# overall.net
KiCad netlist of a schematic drawn in Altium Designer
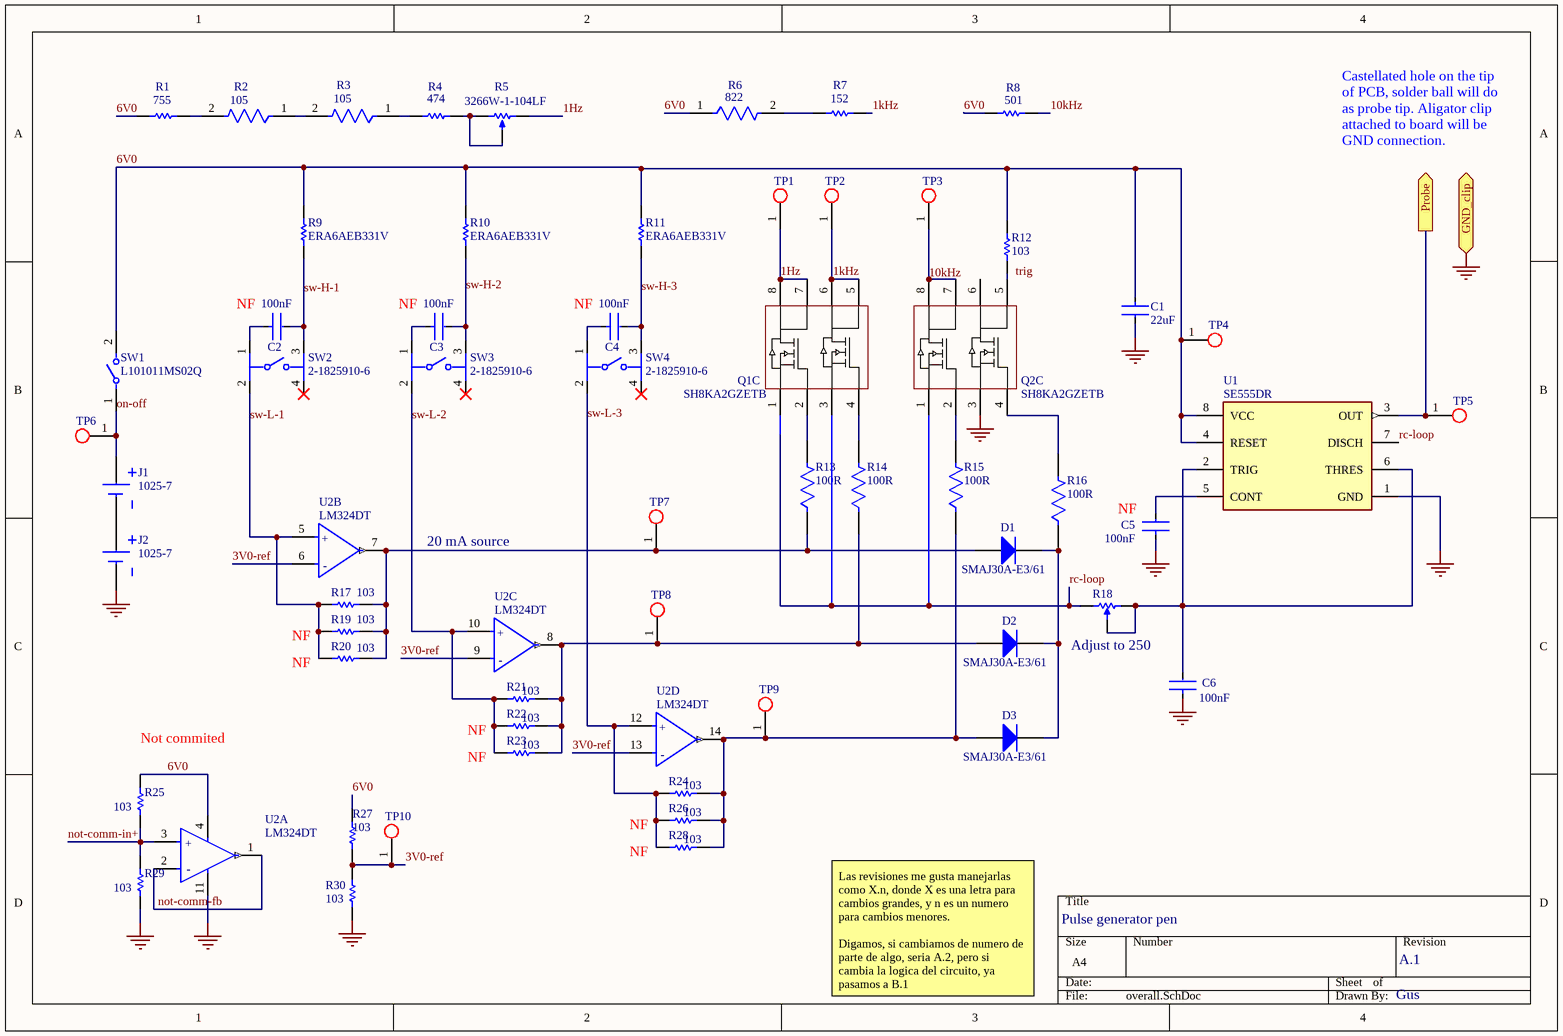
[diagram p0: overall.SchDoc]

(export (version "E")
  (design (tool "Eeschema 10.0.6"))
  (components
    (comp (ref "C1")
      (value "C2012X5R1V226M125AC")
      (footprint "FP-C2012-125-0_2-IPC_A")
      (description "Multilayer Ceramic Capacitors 22μF ±20% 35V X5R SMD 0805")
      (fields (field (name "TOLERANCE") "20%") (field (name "CAPACITANCE") "22uF"))
      (libsource (lib "Altium Content Vault") (part "b4654b650e69147ec39a6b967a45e02"))
    )
    (comp (ref "C2")
      (value "CL21B104KBCNNNC")
      (footprint "FP-CL21-IPC_A")
      (description "CL21 Series 0805 100nF 50V ±10% Tolerance X7R Multilayer Ceramic Chip Capacitor")
      (fields
        (field (name "TOLERANCE") "10%")
        (field (name "CAPACITANCE") "100nF")
        (field (name "VOLTAGE") "50V")
      )
      (libsource (lib "Altium Content Vault") (part "b4654b650e69147ec39a6b967a45e02"))
    )
    (comp (ref "C3")
      (value "CL21B104KBCNNNC")
      (footprint "FP-CL21-IPC_A")
      (description "CL21 Series 0805 100nF 50V ±10% Tolerance X7R Multilayer Ceramic Chip Capacitor")
      (fields
        (field (name "TOLERANCE") "10%")
        (field (name "CAPACITANCE") "100nF")
        (field (name "VOLTAGE") "50V")
      )
      (libsource (lib "Altium Content Vault") (part "b4654b650e69147ec39a6b967a45e02"))
    )
    (comp (ref "C4")
      (value "CL21B104KBCNNNC")
      (footprint "FP-CL21-IPC_A")
      (description "CL21 Series 0805 100nF 50V ±10% Tolerance X7R Multilayer Ceramic Chip Capacitor")
      (fields
        (field (name "TOLERANCE") "10%")
        (field (name "CAPACITANCE") "100nF")
        (field (name "VOLTAGE") "50V")
      )
      (libsource (lib "Altium Content Vault") (part "b4654b650e69147ec39a6b967a45e02"))
    )
    (comp (ref "C5")
      (value "CL21B104KBCNNNC")
      (footprint "FP-CL21-IPC_A")
      (description "CL21 Series 0805 100nF 50V ±10% Tolerance X7R Multilayer Ceramic Chip Capacitor")
      (fields
        (field (name "TOLERANCE") "10%")
        (field (name "CAPACITANCE") "100nF")
        (field (name "VOLTAGE") "50V")
      )
      (libsource (lib "Altium Content Vault") (part "b4654b650e69147ec39a6b967a45e02"))
    )
    (comp (ref "C6")
      (value "CL21B104KBCNNNC")
      (footprint "FP-CL21-IPC_A")
      (description "CL21 Series 0805 100nF 50V ±10% Tolerance X7R Multilayer Ceramic Chip Capacitor")
      (fields
        (field (name "TOLERANCE") "10%")
        (field (name "CAPACITANCE") "100nF")
        (field (name "VOLTAGE") "50V")
      )
      (libsource (lib "Altium Content Vault") (part "b4654b650e69147ec39a6b967a45e02"))
    )
    (comp (ref "D1")
      (value "SMAJ30A-E3/61")
      (footprint "VISH-DO-214AC-2_N")
      (fields (field (name "MANUFACTURER") "Vishay Semiconductor"))
      (libsource (lib "Altium Content Vault") (part "VISH-K1A2-2"))
    )
    (comp (ref "D2")
      (value "SMAJ30A-E3/61")
      (footprint "VISH-DO-214AC-2_N")
      (fields (field (name "MANUFACTURER") "Vishay Semiconductor"))
      (libsource (lib "Altium Content Vault") (part "VISH-K1A2-2"))
    )
    (comp (ref "D3")
      (value "SMAJ30A-E3/61")
      (footprint "VISH-DO-214AC-2_N")
      (fields (field (name "MANUFACTURER") "Vishay Semiconductor"))
      (libsource (lib "Altium Content Vault") (part "VISH-K1A2-2"))
    )
    (comp (ref "J1")
      (value "1025-7")
      (footprint "KEYSTONE-1025-7-2_V")
      (description "Holder for 2477 or 2430 Cells P/N 1025-7, Body 27.762 x 30.963 mm, THM")
      (fields (field (name "MANUFACTURER") "Keystone"))
      (libsource (lib "Altium Content Vault") (part "KEYSTONE-1025-7-2"))
    )
    (comp (ref "J2")
      (value "1025-7")
      (footprint "KEYSTONE-1025-7-2_V")
      (description "Holder for 2477 or 2430 Cells P/N 1025-7, Body 27.762 x 30.963 mm, THM")
      (fields (field (name "MANUFACTURER") "Keystone"))
      (libsource (lib "Altium Content Vault") (part "KEYSTONE-1025-7-2"))
    )
    (comp (ref "Q1")
      (value "SH8KA2GZETB")
      (footprint "SOIC127P600X175-8N")
      (libsource (lib "Cetys University") (part "SH8KA2GZETB"))
    )
    (comp (ref "Q2")
      (value "SH8KA2GZETB")
      (footprint "SOIC127P600X175-8N")
      (libsource (lib "Cetys University") (part "SH8KA2GZETB"))
    )
    (comp (ref "R1")
      (value "CRCW08057M50JNEA")
      (footprint "RESC2013X50X30LL20T20")
      (fields (field (name "MANUFACTURER") "Vishay Dale") (field (name "RESISTANCE") "755"))
      (libsource (lib "Altium Content Vault") (part "RES"))
    )
    (comp (ref "R2")
      (value "ERJ-6ENF1004V")
      (footprint "FP-ERJ6EN-IPC_A")
      (description "RES SMD 1M OHM 1% 1/8W 0805")
      (fields (field (name "RESISTANCE") "105") (field (name "TOLERANCE") "1%"))
      (libsource (lib "Altium Content Vault") (part "1029c3af85768c4190bb7ad29bc67b5"))
    )
    (comp (ref "R3")
      (value "ERJ-6ENF1004V")
      (footprint "FP-ERJ6EN-IPC_A")
      (description "RES SMD 1M OHM 1% 1/8W 0805")
      (fields (field (name "RESISTANCE") "105") (field (name "TOLERANCE") "1%"))
      (libsource (lib "Altium Content Vault") (part "1029c3af85768c4190bb7ad29bc67b5"))
    )
    (comp (ref "R4")
      (value "ERJ6ENF4703V")
      (footprint "RESC2013X70X40ML20T20")
      (fields (field (name "MANUFACTURER") "Panasonic") (field (name "RESISTANCE") "474"))
      (libsource (lib "Altium Content Vault") (part "RES"))
    )
    (comp (ref "R5")
      (value "3266W-1-104LF")
      (footprint "BOUR-3266W-3_V")
      (description "Square Trimpot Trimming Potentiometer, 100 KOhm, 0.25 W, -55 to 125 degC, 3-Pin THD, RoHS, Tube")
      (fields (field (name "TOLERANCE") "+/-10%") (field (name "MANUFACTURER") "Bourns"))
      (libsource (lib "Altium Content Vault") (part "BOUR-POT-3"))
    )
    (comp (ref "R6")
      (value "RC2012J822CS")
      (footprint "FP-RC2012-IPC_A")
      (description "Res Thick Film 0805 8.2kΩ 5% 0.125W ±100ppm/°C Molded SMD T/R")
      (fields (field (name "RESISTANCE") "822") (field (name "TOLERANCE") "5%"))
      (libsource (lib "Altium Content Vault") (part "1029c3af85768c4190bb7ad29bc67b5"))
    )
    (comp (ref "R7")
      (value "RC0805FR-071K5L")
      (footprint "RESC2013X60X35LL10T20")
      (description "RES 1.50K OHM 1/8W 1% 0805 SMD")
      (fields (field (name "MANUFACTURER") "Yageo") (field (name "RESISTANCE") "152"))
      (libsource (lib "") (part "RES-2_1"))
    )
    (comp (ref "R8")
      (value "WSLP0805R0500FEA")
      (footprint "RESC2013X58X38LL25T25")
      (fields (field (name "MANUFACTURER") "Vishay Dale") (field (name "RESISTANCE") "501"))
      (libsource (lib "Altium Content Vault") (part "RES"))
    )
    (comp (ref "R9")
      (value "ERA6AEB331V")
      (footprint "RESC2013X60X40LL20T25")
      (fields (field (name "MANUFACTURER") "Panasonic"))
      (libsource (lib "Altium Content Vault") (part "RES"))
    )
    (comp (ref "R10")
      (value "ERA6AEB331V")
      (footprint "RESC2013X60X40LL20T25")
      (fields (field (name "MANUFACTURER") "Panasonic"))
      (libsource (lib "Altium Content Vault") (part "RES"))
    )
    (comp (ref "R11")
      (value "ERA6AEB331V")
      (footprint "RESC2013X60X40LL20T25")
      (fields (field (name "MANUFACTURER") "Panasonic"))
      (libsource (lib "Altium Content Vault") (part "RES"))
    )
    (comp (ref "R12")
      (value "RC0805FR-0710KL")
      (footprint "RESC2013X60X35NL10T20")
      (description "Chip Resistor, 10 KOhm, +/- 1%, 0.125 W, -55 to 155 degC, 0805 (2012 Metric), RoHS, Tape and Reel")
      (fields (field (name "MANUFACTURER") "Yageo") (field (name "RESISTANCE") "103"))
      (libsource (lib "Altium Content Vault") (part "RES-2"))
    )
    (comp (ref "R13")
      (value "CRCW0805100RFKEAHP")
      (footprint "FP-CRCW0805-HPe3-IPC_A")
      (description "RES Thick Film, 100Ω, 1%, 0.5W, 100ppm/°C, 0805")
      (fields (field (name "TOLERANCE") "1%") (field (name "RESISTANCE") "100R"))
      (libsource (lib "") (part "1029c3af85768c4190bb7ad29bc67b5_1"))
    )
    (comp (ref "R14")
      (value "CRCW0805100RFKEAHP")
      (footprint "FP-CRCW0805-HPe3-IPC_A")
      (description "RES Thick Film, 100Ω, 1%, 0.5W, 100ppm/°C, 0805")
      (fields (field (name "TOLERANCE") "1%") (field (name "RESISTANCE") "100R"))
      (libsource (lib "") (part "1029c3af85768c4190bb7ad29bc67b5_1"))
    )
    (comp (ref "R15")
      (value "CRCW0805100RFKEAHP")
      (footprint "FP-CRCW0805-HPe3-IPC_A")
      (description "RES Thick Film, 100Ω, 1%, 0.5W, 100ppm/°C, 0805")
      (fields (field (name "TOLERANCE") "1%") (field (name "RESISTANCE") "100R"))
      (libsource (lib "") (part "1029c3af85768c4190bb7ad29bc67b5_1"))
    )
    (comp (ref "R16")
      (value "CRCW0805100RFKEAHP")
      (footprint "FP-CRCW0805-HPe3-IPC_A")
      (description "RES Thick Film, 100Ω, 1%, 0.5W, 100ppm/°C, 0805")
      (fields (field (name "TOLERANCE") "1%") (field (name "RESISTANCE") "100R"))
      (libsource (lib "") (part "1029c3af85768c4190bb7ad29bc67b5_1"))
    )
    (comp (ref "R17")
      (value "RC0805FR-0710KL")
      (footprint "RESC2013X60X35NL10T20")
      (description "Chip Resistor, 10 KOhm, +/- 1%, 0.125 W, -55 to 155 degC, 0805 (2012 Metric), RoHS, Tape and Reel")
      (fields (field (name "MANUFACTURER") "Yageo") (field (name "RESISTANCE") "103"))
      (libsource (lib "Altium Content Vault") (part "RES-2"))
    )
    (comp (ref "R18")
      (value "3296W-1-102LF")
      (footprint "BOUR-3296W-1-3")
      (description "Square Trimpot(R) Trimming Potentiometer, 1000 Ohm, -55 to 125 degC, 3-Pin THD, RoHS, Tube")
      (fields (field (name "TOLERANCE") "1%"))
      (libsource (lib "Altium Content Vault") (part "RES-ADJ-3"))
    )
    (comp (ref "R19")
      (value "RC0805FR-0710KL")
      (footprint "RESC2013X60X35NL10T20")
      (description "Chip Resistor, 10 KOhm, +/- 1%, 0.125 W, -55 to 155 degC, 0805 (2012 Metric), RoHS, Tape and Reel")
      (fields (field (name "MANUFACTURER") "Yageo") (field (name "RESISTANCE") "103"))
      (libsource (lib "Altium Content Vault") (part "RES-2"))
    )
    (comp (ref "R20")
      (value "RC0805FR-0710KL")
      (footprint "RESC2013X60X35NL10T20")
      (description "Chip Resistor, 10 KOhm, +/- 1%, 0.125 W, -55 to 155 degC, 0805 (2012 Metric), RoHS, Tape and Reel")
      (fields (field (name "MANUFACTURER") "Yageo") (field (name "RESISTANCE") "103"))
      (libsource (lib "Altium Content Vault") (part "RES-2"))
    )
    (comp (ref "R21")
      (value "RC0805FR-0710KL")
      (footprint "RESC2013X60X35NL10T20")
      (description "Chip Resistor, 10 KOhm, +/- 1%, 0.125 W, -55 to 155 degC, 0805 (2012 Metric), RoHS, Tape and Reel")
      (fields (field (name "MANUFACTURER") "Yageo") (field (name "RESISTANCE") "103"))
      (libsource (lib "Altium Content Vault") (part "RES-2"))
    )
    (comp (ref "R22")
      (value "RC0805FR-0710KL")
      (footprint "RESC2013X60X35NL10T20")
      (description "Chip Resistor, 10 KOhm, +/- 1%, 0.125 W, -55 to 155 degC, 0805 (2012 Metric), RoHS, Tape and Reel")
      (fields (field (name "MANUFACTURER") "Yageo") (field (name "RESISTANCE") "103"))
      (libsource (lib "Altium Content Vault") (part "RES-2"))
    )
    (comp (ref "R23")
      (value "RC0805FR-0710KL")
      (footprint "RESC2013X60X35NL10T20")
      (description "Chip Resistor, 10 KOhm, +/- 1%, 0.125 W, -55 to 155 degC, 0805 (2012 Metric), RoHS, Tape and Reel")
      (fields (field (name "MANUFACTURER") "Yageo") (field (name "RESISTANCE") "103"))
      (libsource (lib "Altium Content Vault") (part "RES-2"))
    )
    (comp (ref "R24")
      (value "RC0805FR-0710KL")
      (footprint "RESC2013X60X35NL10T20")
      (description "Chip Resistor, 10 KOhm, +/- 1%, 0.125 W, -55 to 155 degC, 0805 (2012 Metric), RoHS, Tape and Reel")
      (fields (field (name "MANUFACTURER") "Yageo") (field (name "RESISTANCE") "103"))
      (libsource (lib "Altium Content Vault") (part "RES-2"))
    )
    (comp (ref "R25")
      (value "RC0805FR-0710KL")
      (footprint "RESC2013X60X35NL10T20")
      (description "Chip Resistor, 10 KOhm, +/- 1%, 0.125 W, -55 to 155 degC, 0805 (2012 Metric), RoHS, Tape and Reel")
      (fields (field (name "MANUFACTURER") "Yageo") (field (name "RESISTANCE") "103"))
      (libsource (lib "Altium Content Vault") (part "RES-2"))
    )
    (comp (ref "R26")
      (value "RC0805FR-0710KL")
      (footprint "RESC2013X60X35NL10T20")
      (description "Chip Resistor, 10 KOhm, +/- 1%, 0.125 W, -55 to 155 degC, 0805 (2012 Metric), RoHS, Tape and Reel")
      (fields (field (name "MANUFACTURER") "Yageo") (field (name "RESISTANCE") "103"))
      (libsource (lib "Altium Content Vault") (part "RES-2"))
    )
    (comp (ref "R27")
      (value "RC0805FR-0710KL")
      (footprint "RESC2013X60X35NL10T20")
      (description "Chip Resistor, 10 KOhm, +/- 1%, 0.125 W, -55 to 155 degC, 0805 (2012 Metric), RoHS, Tape and Reel")
      (fields (field (name "MANUFACTURER") "Yageo") (field (name "RESISTANCE") "103"))
      (libsource (lib "Altium Content Vault") (part "RES-2"))
    )
    (comp (ref "R28")
      (value "RC0805FR-0710KL")
      (footprint "RESC2013X60X35NL10T20")
      (description "Chip Resistor, 10 KOhm, +/- 1%, 0.125 W, -55 to 155 degC, 0805 (2012 Metric), RoHS, Tape and Reel")
      (fields (field (name "MANUFACTURER") "Yageo") (field (name "RESISTANCE") "103"))
      (libsource (lib "Altium Content Vault") (part "RES-2"))
    )
    (comp (ref "R29")
      (value "RC0805FR-0710KL")
      (footprint "RESC2013X60X35NL10T20")
      (description "Chip Resistor, 10 KOhm, +/- 1%, 0.125 W, -55 to 155 degC, 0805 (2012 Metric), RoHS, Tape and Reel")
      (fields (field (name "MANUFACTURER") "Yageo") (field (name "RESISTANCE") "103"))
      (libsource (lib "Altium Content Vault") (part "RES-2"))
    )
    (comp (ref "R30")
      (value "RC0805FR-0710KL")
      (footprint "RESC2013X60X35NL10T20")
      (description "Chip Resistor, 10 KOhm, +/- 1%, 0.125 W, -55 to 155 degC, 0805 (2012 Metric), RoHS, Tape and Reel")
      (fields (field (name "MANUFACTURER") "Yageo") (field (name "RESISTANCE") "103"))
      (libsource (lib "Altium Content Vault") (part "RES-2"))
    )
    (comp (ref "SW1")
      (value "L101011MS02Q")
      (footprint "FP-L101011MS02Q-MFG")
      (description "SWITCH SLIDE SPST 4A 125V")
      (libsource (lib "Altium Content Vault") (part "bb27bde45df87f1f469753f287ef5ae"))
    )
    (comp (ref "SW2")
      (value "2-1825910-6")
      (footprint "FP-2-1825910-6-MFG")
      (description "SWITCH TACTILE SPST-NO 0.05A 24V")
      (libsource (lib "Altium Content Vault") (part "b8895f3f4cefb76e1819d2863dba89b"))
    )
    (comp (ref "SW3")
      (value "2-1825910-6")
      (footprint "FP-2-1825910-6-MFG")
      (description "SWITCH TACTILE SPST-NO 0.05A 24V")
      (libsource (lib "Altium Content Vault") (part "b8895f3f4cefb76e1819d2863dba89b"))
    )
    (comp (ref "SW4")
      (value "2-1825910-6")
      (footprint "FP-2-1825910-6-MFG")
      (description "SWITCH TACTILE SPST-NO 0.05A 24V")
      (libsource (lib "Altium Content Vault") (part "b8895f3f4cefb76e1819d2863dba89b"))
    )
    (comp (ref "TP1")
      (value "TP_opening")
      (footprint "New footprint 1")
      (description "Soldermask opening or top layer pad for testing purposes")
      (libsource (lib "Cetys University") (part "TP1"))
    )
    (comp (ref "TP2")
      (value "TP_opening")
      (footprint "New footprint 1")
      (description "Soldermask opening or top layer pad for testing purposes")
      (libsource (lib "Cetys University") (part "TP1"))
    )
    (comp (ref "TP3")
      (value "TP_opening")
      (footprint "New footprint 1")
      (description "Soldermask opening or top layer pad for testing purposes")
      (libsource (lib "Cetys University") (part "TP1"))
    )
    (comp (ref "TP4")
      (value "TP_opening")
      (footprint "New footprint 1")
      (description "Soldermask opening or top layer pad for testing purposes")
      (libsource (lib "Cetys University") (part "TP1"))
    )
    (comp (ref "TP5")
      (value "TP_opening")
      (footprint "New footprint 1")
      (description "Soldermask opening or top layer pad for testing purposes")
      (libsource (lib "Cetys University") (part "TP1"))
    )
    (comp (ref "TP6")
      (value "TP_opening")
      (footprint "New footprint 1")
      (description "Soldermask opening or top layer pad for testing purposes")
      (libsource (lib "Cetys University") (part "TP1"))
    )
    (comp (ref "TP7")
      (value "TP_opening")
      (footprint "New footprint 1")
      (description "Soldermask opening or top layer pad for testing purposes")
      (libsource (lib "Cetys University") (part "TP1"))
    )
    (comp (ref "TP8")
      (value "TP_opening")
      (footprint "New footprint 1")
      (description "Soldermask opening or top layer pad for testing purposes")
      (libsource (lib "Cetys University") (part "TP1"))
    )
    (comp (ref "TP9")
      (value "TP_opening")
      (footprint "New footprint 1")
      (description "Soldermask opening or top layer pad for testing purposes")
      (libsource (lib "Cetys University") (part "TP1"))
    )
    (comp (ref "TP10")
      (value "TP_opening")
      (footprint "New footprint 1")
      (description "Soldermask opening or top layer pad for testing purposes")
      (libsource (lib "Cetys University") (part "TP1"))
    )
    (comp (ref "U1")
      (value "SE555DR")
      (footprint "FP-D0008A-MFG")
      (description "IC OSC SGL TIMER 100KHZ 8-SOIC")
      (libsource (lib "Altium Content Vault") (part "dd5b8434f2346953fd8290325fbf3de"))
    )
    (comp (ref "U2")
      (value "LM324DT")
      (footprint "FP-SO-14-MFG")
      (description "IC OPAMP GP 4 CIRCUIT 14SO")
      (fields
        (field (name "OCTOPART") "https://octopart.com/lm324dt-stmicroelectronics-39579146")
        (field (name "MANUFACTURER") "STMicroelectronics")
      )
      (libsource (lib "Altium Content Vault") (part "a065ef67e5aa9ef3942d43d6008d043"))
    )
  )
  (nets
    (net (code "1") (name "/1Hz") (class "Default")
      (node (ref "Q1") (pin "7") (pinfunction "7_7") (pintype "passive"))
      (node (ref "Q1") (pin "8") (pinfunction "8_8") (pintype "passive"))
      (node (ref "R5") (pin "3") (pinfunction "CW_3") (pintype "passive"))
      (node (ref "TP1") (pin "1") (pinfunction "1_1") (pintype "passive"))
    )
    (net (code "2") (name "/1kHz") (class "Default")
      (node (ref "Q1") (pin "5") (pinfunction "5_5") (pintype "passive"))
      (node (ref "Q1") (pin "6") (pinfunction "6_6") (pintype "passive"))
      (node (ref "R7") (pin "2") (pinfunction "2_2") (pintype "passive"))
      (node (ref "TP2") (pin "1") (pinfunction "1_1") (pintype "passive"))
    )
    (net (code "3") (name "/3V0-ref") (class "Default")
      (node (ref "R27") (pin "1") (pinfunction "1_1") (pintype "passive"))
      (node (ref "R30") (pin "2") (pinfunction "2_2") (pintype "passive"))
      (node (ref "TP10") (pin "1") (pinfunction "1_1") (pintype "passive"))
      (node (ref "U2") (pin "13") (pinfunction "Inverting_Input_4_13") (pintype "tri_state"))
      (node (ref "U2") (pin "6") (pinfunction "Inverting_Input_2_6") (pintype "tri_state"))
      (node (ref "U2") (pin "9") (pinfunction "Inverting_Input_3_9") (pintype "tri_state"))
    )
    (net (code "4") (name "/6V0") (class "Default")
      (node (ref "C1") (pin "1") (pinfunction "1_1") (pintype "passive"))
      (node (ref "R1") (pin "2") (pinfunction "2_2") (pintype "passive"))
      (node (ref "R10") (pin "1") (pinfunction "1_1") (pintype "passive"))
      (node (ref "R11") (pin "1") (pinfunction "1_1") (pintype "passive"))
      (node (ref "R12") (pin "1") (pinfunction "1_1") (pintype "passive"))
      (node (ref "R25") (pin "2") (pinfunction "2_2") (pintype "passive"))
      (node (ref "R27") (pin "2") (pinfunction "2_2") (pintype "passive"))
      (node (ref "R6") (pin "1") (pinfunction "1_1") (pintype "passive"))
      (node (ref "R8") (pin "1") (pinfunction "1_1") (pintype "passive"))
      (node (ref "R9") (pin "1") (pinfunction "1_1") (pintype "passive"))
      (node (ref "SW1") (pin "2") (pinfunction "2_2") (pintype "passive"))
      (node (ref "TP4") (pin "1") (pinfunction "1_1") (pintype "passive"))
      (node (ref "U1") (pin "4") (pinfunction "RESET_4") (pintype "passive"))
      (node (ref "U1") (pin "8") (pinfunction "VCC_8") (pintype "power_in"))
      (node (ref "U2") (pin "4") (pinfunction "VCC+_4") (pintype "power_in"))
    )
    (net (code "5") (name "/10kHz") (class "Default")
      (node (ref "Q2") (pin "7") (pinfunction "7_7") (pintype "passive"))
      (node (ref "Q2") (pin "8") (pinfunction "8_8") (pintype "passive"))
      (node (ref "R8") (pin "2") (pinfunction "2_2") (pintype "passive"))
      (node (ref "TP3") (pin "1") (pinfunction "1_1") (pintype "passive"))
    )
    (net (code "6") (name "/Probe") (class "Default")
      (node (ref "TP5") (pin "1") (pinfunction "1_1") (pintype "passive"))
      (node (ref "U1") (pin "3") (pinfunction "OUT_3") (pintype "output"))
    )
    (net (code "7") (name "/not-comm-fb") (class "Default")
      (node (ref "U2") (pin "1") (pinfunction "Output_1_1") (pintype "output"))
      (node (ref "U2") (pin "2") (pinfunction "Inverting_Input_1_2") (pintype "tri_state"))
    )
    (net (code "8") (name "/not-comm-in+") (class "Default")
      (node (ref "R25") (pin "1") (pinfunction "1_1") (pintype "passive"))
      (node (ref "R29") (pin "2") (pinfunction "2_2") (pintype "passive"))
      (node (ref "U2") (pin "3") (pinfunction "Non-Inverting_Input_1_3") (pintype "tri_state"))
    )
    (net (code "9") (name "/on-off") (class "Default")
      (node (ref "J1") (pin "1") (pinfunction "+_1") (pintype "passive"))
      (node (ref "SW1") (pin "1") (pinfunction "1_1") (pintype "passive"))
      (node (ref "TP6") (pin "1") (pinfunction "1_1") (pintype "passive"))
    )
    (net (code "10") (name "/rc-loop") (class "Default")
      (node (ref "Q1") (pin "1") (pinfunction "1_1") (pintype "passive"))
      (node (ref "Q1") (pin "3") (pinfunction "3_3") (pintype "passive"))
      (node (ref "Q2") (pin "1") (pinfunction "1_1") (pintype "passive"))
      (node (ref "R18") (pin "1") (pinfunction "A_1") (pintype "passive"))
      (node (ref "U1") (pin "7") (pinfunction "DISCH_7") (pintype "passive"))
    )
    (net (code "11") (name "/sw-H-1") (class "Default")
      (node (ref "C2") (pin "2") (pinfunction "2_2") (pintype "passive"))
      (node (ref "R9") (pin "2") (pinfunction "2_2") (pintype "passive"))
      (node (ref "SW2") (pin "3") (pinfunction "3_3") (pintype "passive"))
    )
    (net (code "12") (name "/sw-H-2") (class "Default")
      (node (ref "C3") (pin "2") (pinfunction "2_2") (pintype "passive"))
      (node (ref "R10") (pin "2") (pinfunction "2_2") (pintype "passive"))
      (node (ref "SW3") (pin "3") (pinfunction "3_3") (pintype "passive"))
    )
    (net (code "13") (name "/sw-H-3") (class "Default")
      (node (ref "C4") (pin "2") (pinfunction "2_2") (pintype "passive"))
      (node (ref "R11") (pin "2") (pinfunction "2_2") (pintype "passive"))
      (node (ref "SW4") (pin "3") (pinfunction "3_3") (pintype "passive"))
    )
    (net (code "14") (name "/sw-L-1") (class "Default")
      (node (ref "R17") (pin "2") (pinfunction "2_2") (pintype "passive"))
      (node (ref "R19") (pin "2") (pinfunction "2_2") (pintype "passive"))
      (node (ref "R20") (pin "2") (pinfunction "2_2") (pintype "passive"))
      (node (ref "SW2") (pin "2") (pinfunction "2_2") (pintype "passive"))
      (node (ref "U2") (pin "5") (pinfunction "Non-Inverting_Input_2_5") (pintype "tri_state"))
    )
    (net (code "15") (name "/sw-L-2") (class "Default")
      (node (ref "R21") (pin "2") (pinfunction "2_2") (pintype "passive"))
      (node (ref "R22") (pin "2") (pinfunction "2_2") (pintype "passive"))
      (node (ref "R23") (pin "2") (pinfunction "2_2") (pintype "passive"))
      (node (ref "SW3") (pin "2") (pinfunction "2_2") (pintype "passive"))
      (node (ref "U2") (pin "10") (pinfunction "Non-Inverting_Input_3_10") (pintype "tri_state"))
    )
    (net (code "16") (name "/sw-L-3") (class "Default")
      (node (ref "R24") (pin "2") (pinfunction "2_2") (pintype "passive"))
      (node (ref "R26") (pin "2") (pinfunction "2_2") (pintype "passive"))
      (node (ref "R28") (pin "2") (pinfunction "2_2") (pintype "passive"))
      (node (ref "SW4") (pin "2") (pinfunction "2_2") (pintype "passive"))
      (node (ref "U2") (pin "12") (pinfunction "Non-Inverting_Input_4_12") (pintype "tri_state"))
    )
    (net (code "18") (name "GND") (class "Default")
      (node (ref "C1") (pin "2") (pinfunction "2_2") (pintype "passive"))
      (node (ref "C5") (pin "1") (pinfunction "1_1") (pintype "passive"))
      (node (ref "C6") (pin "1") (pinfunction "1_1") (pintype "passive"))
      (node (ref "J2") (pin "2") (pinfunction "-_2") (pintype "passive"))
      (node (ref "Q2") (pin "3") (pinfunction "3_3") (pintype "passive"))
      (node (ref "R29") (pin "1") (pinfunction "1_1") (pintype "passive"))
      (node (ref "R30") (pin "1") (pinfunction "1_1") (pintype "passive"))
      (node (ref "U1") (pin "1") (pinfunction "GND_1") (pintype "power_in"))
      (node (ref "U2") (pin "11") (pinfunction "VCC-_11") (pintype "power_in"))
    )
    (net (code "19") (name "Net-(C2-Pad1)") (class "Default")
      (node (ref "C2") (pin "1") (pinfunction "1_1") (pintype "passive"))
      (node (ref "SW2") (pin "1") (pinfunction "1_1") (pintype "passive"))
    )
    (net (code "20") (name "Net-(C3-Pad1)") (class "Default")
      (node (ref "C3") (pin "1") (pinfunction "1_1") (pintype "passive"))
      (node (ref "SW3") (pin "1") (pinfunction "1_1") (pintype "passive"))
    )
    (net (code "21") (name "Net-(C4-Pad1)") (class "Default")
      (node (ref "C4") (pin "1") (pinfunction "1_1") (pintype "passive"))
      (node (ref "SW4") (pin "1") (pinfunction "1_1") (pintype "passive"))
    )
    (net (code "22") (name "Net-(D1-A)") (class "Default")
      (node (ref "D1") (pin "2") (pinfunction "A_2") (pintype "passive"))
      (node (ref "R13") (pin "1") (pinfunction "1_1") (pintype "passive"))
      (node (ref "R17") (pin "1") (pinfunction "1_1") (pintype "passive"))
      (node (ref "R19") (pin "1") (pinfunction "1_1") (pintype "passive"))
      (node (ref "R20") (pin "1") (pinfunction "1_1") (pintype "passive"))
      (node (ref "TP7") (pin "1") (pinfunction "1_1") (pintype "passive"))
      (node (ref "U2") (pin "7") (pinfunction "Output_2_7") (pintype "output"))
    )
    (net (code "23") (name "Net-(D1-K)") (class "Default")
      (node (ref "D1") (pin "1") (pinfunction "K_1") (pintype "passive"))
      (node (ref "D2") (pin "1") (pinfunction "K_1") (pintype "passive"))
      (node (ref "D3") (pin "1") (pinfunction "K_1") (pintype "passive"))
      (node (ref "R16") (pin "1") (pinfunction "1_1") (pintype "passive"))
    )
    (net (code "24") (name "Net-(D2-A)") (class "Default")
      (node (ref "D2") (pin "2") (pinfunction "A_2") (pintype "passive"))
      (node (ref "R14") (pin "1") (pinfunction "1_1") (pintype "passive"))
      (node (ref "R21") (pin "1") (pinfunction "1_1") (pintype "passive"))
      (node (ref "R22") (pin "1") (pinfunction "1_1") (pintype "passive"))
      (node (ref "R23") (pin "1") (pinfunction "1_1") (pintype "passive"))
      (node (ref "TP8") (pin "1") (pinfunction "1_1") (pintype "passive"))
      (node (ref "U2") (pin "8") (pinfunction "Output_3_8") (pintype "output"))
    )
    (net (code "25") (name "Net-(D3-A)") (class "Default")
      (node (ref "D3") (pin "2") (pinfunction "A_2") (pintype "passive"))
      (node (ref "R15") (pin "1") (pinfunction "1_1") (pintype "passive"))
      (node (ref "R24") (pin "1") (pinfunction "1_1") (pintype "passive"))
      (node (ref "R26") (pin "1") (pinfunction "1_1") (pintype "passive"))
      (node (ref "R28") (pin "1") (pinfunction "1_1") (pintype "passive"))
      (node (ref "TP9") (pin "1") (pinfunction "1_1") (pintype "passive"))
      (node (ref "U2") (pin "14") (pinfunction "Output_4_14") (pintype "output"))
    )
    (net (code "26") (name "Net-(J1--)") (class "Default")
      (node (ref "J1") (pin "2") (pinfunction "-_2") (pintype "passive"))
      (node (ref "J2") (pin "1") (pinfunction "+_1") (pintype "passive"))
    )
    (net (code "27") (name "Net-(Q1-Pad2)") (class "Default")
      (node (ref "Q1") (pin "2") (pinfunction "2_2") (pintype "passive"))
      (node (ref "R13") (pin "2") (pinfunction "2_2") (pintype "passive"))
    )
    (net (code "28") (name "Net-(Q1-Pad4)") (class "Default")
      (node (ref "Q1") (pin "4") (pinfunction "4_4") (pintype "passive"))
      (node (ref "R14") (pin "2") (pinfunction "2_2") (pintype "passive"))
    )
    (net (code "29") (name "Net-(Q2-Pad2)") (class "Default")
      (node (ref "Q2") (pin "2") (pinfunction "2_2") (pintype "passive"))
      (node (ref "R15") (pin "2") (pinfunction "2_2") (pintype "passive"))
    )
    (net (code "30") (name "Net-(Q2-Pad4)") (class "Default")
      (node (ref "Q2") (pin "4") (pinfunction "4_4") (pintype "passive"))
      (node (ref "R16") (pin "2") (pinfunction "2_2") (pintype "passive"))
    )
    (net (code "31") (name "Net-(Q2-Pad5)") (class "Default")
      (node (ref "Q2") (pin "5") (pinfunction "5_5") (pintype "passive"))
      (node (ref "R12") (pin "2") (pinfunction "2_2") (pintype "passive"))
    )
    (net (code "32") (name "Net-(R1-Pad1)") (class "Default")
      (node (ref "R1") (pin "1") (pinfunction "1_1") (pintype "passive"))
      (node (ref "R2") (pin "2") (pinfunction "2_2") (pintype "passive"))
    )
    (net (code "33") (name "Net-(R2-Pad1)") (class "Default")
      (node (ref "R2") (pin "1") (pinfunction "1_1") (pintype "passive"))
      (node (ref "R3") (pin "2") (pinfunction "2_2") (pintype "passive"))
    )
    (net (code "34") (name "Net-(R3-Pad1)") (class "Default")
      (node (ref "R3") (pin "1") (pinfunction "1_1") (pintype "passive"))
      (node (ref "R4") (pin "1") (pinfunction "1_1") (pintype "passive"))
    )
    (net (code "35") (name "Net-(R5-CCW)") (class "Default")
      (node (ref "R4") (pin "2") (pinfunction "2_2") (pintype "passive"))
      (node (ref "R5") (pin "1") (pinfunction "CCW_1") (pintype "passive"))
      (node (ref "R5") (pin "2") (pinfunction "WIPER_2") (pintype "passive"))
    )
    (net (code "36") (name "Net-(R6-Pad2)") (class "Default")
      (node (ref "R6") (pin "2") (pinfunction "2_2") (pintype "passive"))
      (node (ref "R7") (pin "1") (pinfunction "1_1") (pintype "passive"))
    )
    (net (code "37") (name "Net-(R18-B)") (class "Default")
      (node (ref "C6") (pin "2") (pinfunction "2_2") (pintype "passive"))
      (node (ref "R18") (pin "2") (pinfunction "B_2") (pintype "passive"))
      (node (ref "R18") (pin "3") (pinfunction "TAP_3") (pintype "passive"))
      (node (ref "U1") (pin "2") (pinfunction "TRIG_2") (pintype "passive"))
      (node (ref "U1") (pin "6") (pinfunction "THRES_6") (pintype "passive"))
    )
    (net (code "38") (name "Net-(U1-CONT)") (class "Default")
      (node (ref "C5") (pin "2") (pinfunction "2_2") (pintype "passive"))
      (node (ref "U1") (pin "5") (pinfunction "CONT_5") (pintype "passive"))
    )
    (net (code "39") (name "unconnected-(Q2-Pad6)") (class "Default")
      (node (ref "Q2") (pin "6") (pinfunction "6_6") (pintype "passive"))
    )
    (net (code "40") (name "unconnected-(SW2-Pad4)") (class "Default")
      (node (ref "SW2") (pin "4") (pinfunction "4_4") (pintype "passive+no_connect"))
    )
    (net (code "41") (name "unconnected-(SW3-Pad4)") (class "Default")
      (node (ref "SW3") (pin "4") (pinfunction "4_4") (pintype "passive+no_connect"))
    )
    (net (code "42") (name "unconnected-(SW4-Pad4)") (class "Default")
      (node (ref "SW4") (pin "4") (pinfunction "4_4") (pintype "passive+no_connect"))
    )
  )
)
